# InputOutput.net
KiCad netlist of a schematic drawn in Altium Designer
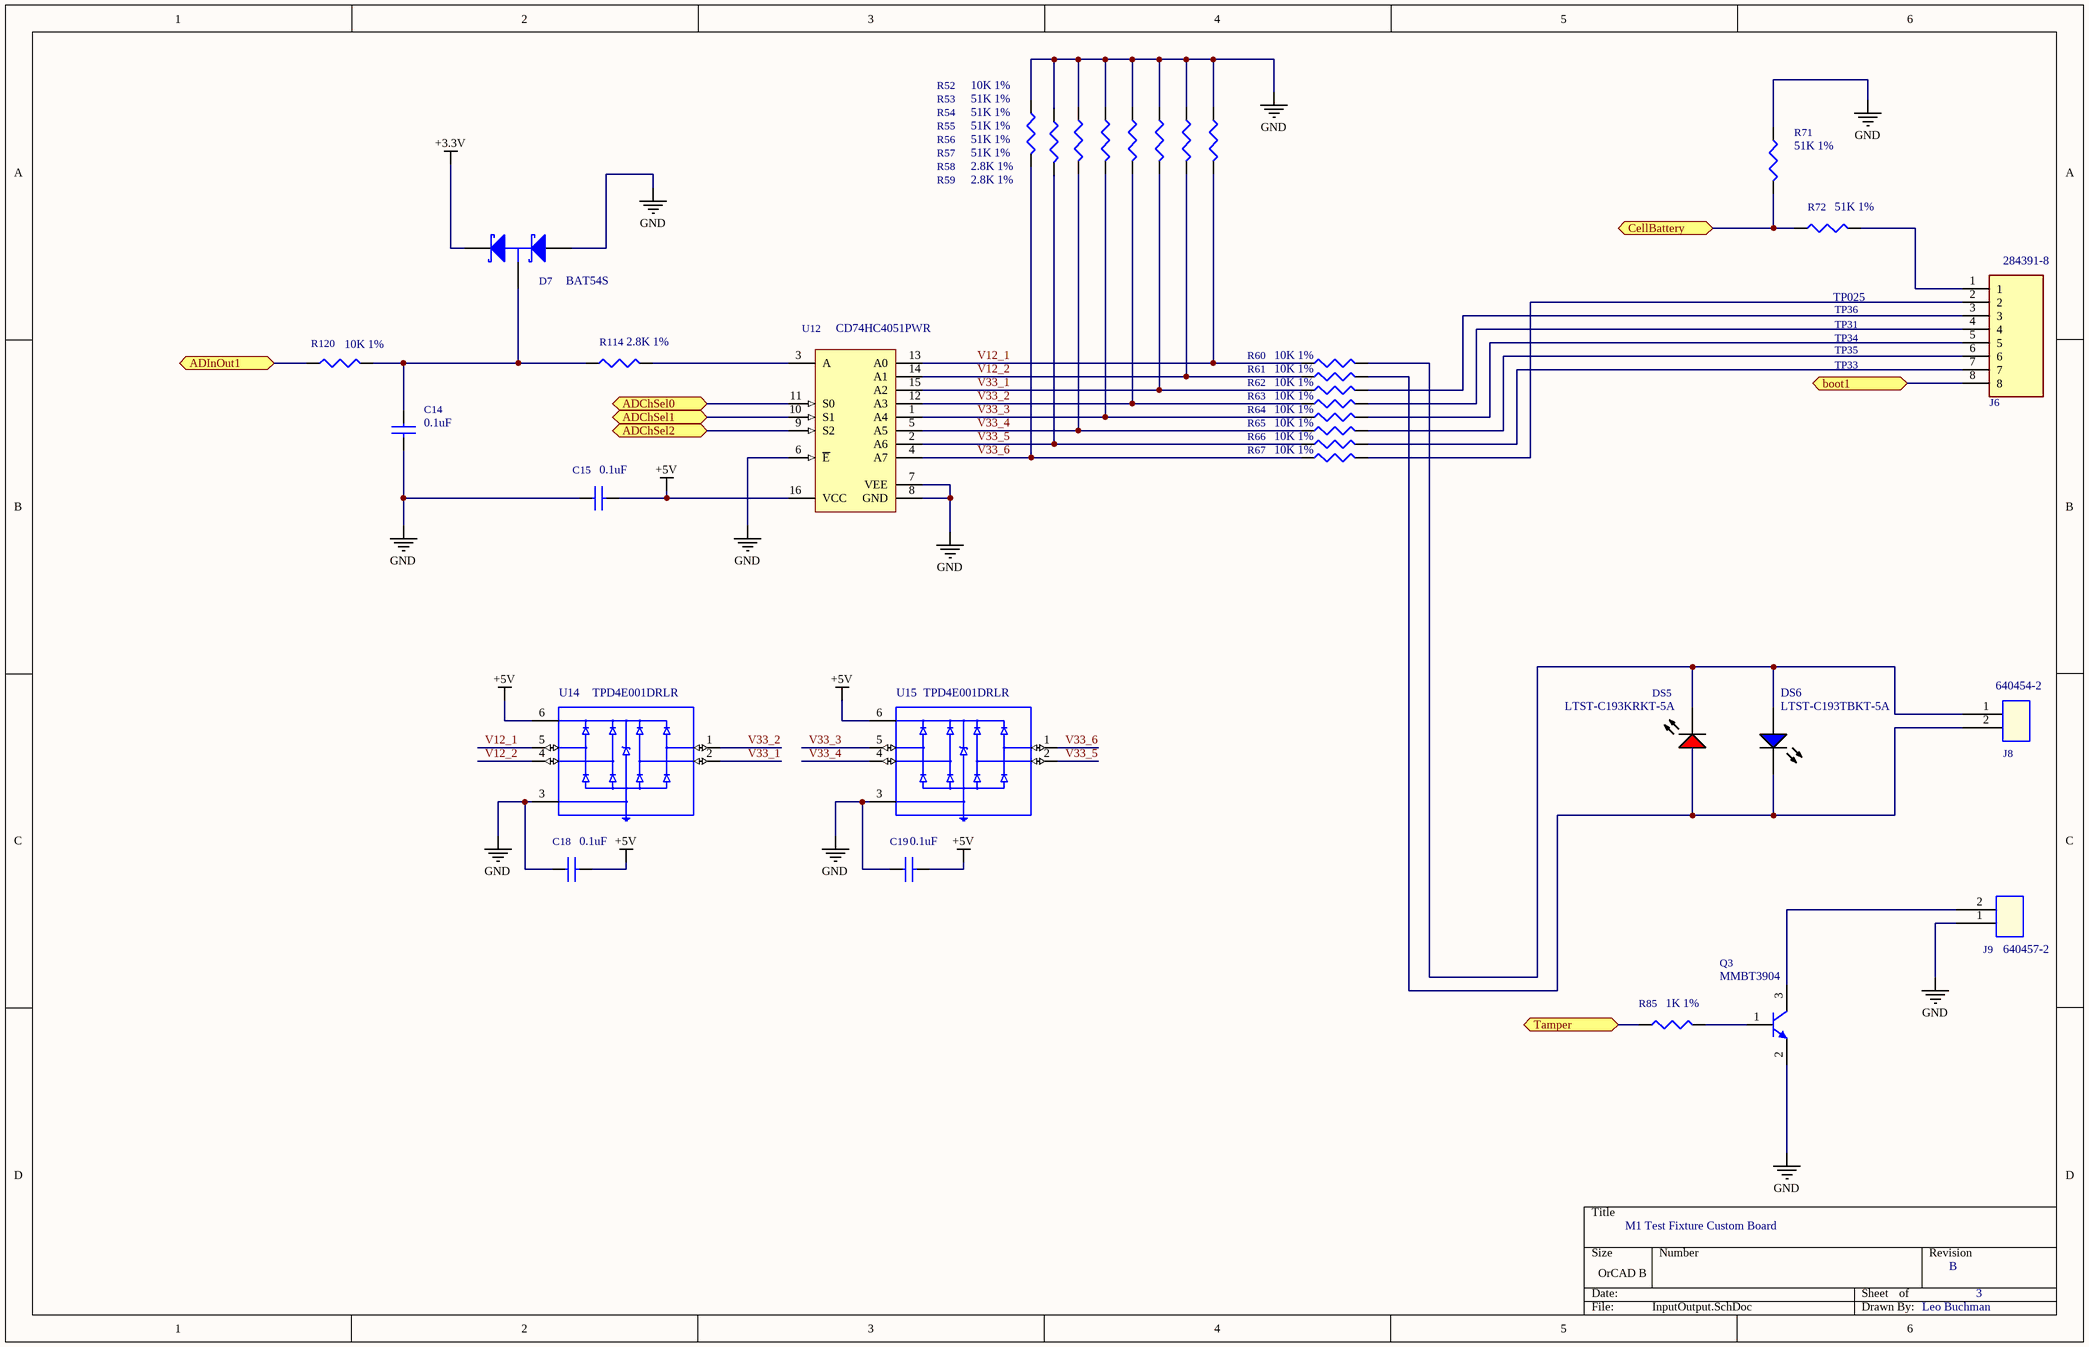
[diagram p0: InputOutput.SchDoc]

(export (version "E")
  (design (tool "Eeschema 10.0.6"))
  (components
    (comp (ref "C14")
      (value "0.1uF")
      (footprint "C0402")
      (description "Cap Ceramic 0.1uF 50V X7R 10% Pad SMD 0402 125C Automotive T/R")
      (fields
        (field (name "MANUFACTURER") "Murata")
        (field (name "MANUFACTURER PART NUMBER") "GRT155R71H104KE01D")
      )
      (libsource (lib "Leo-Home-SQL-Lib") (part "CAPNP"))
    )
    (comp (ref "C15")
      (value "0.1uF")
      (footprint "C0402")
      (description "Cap Ceramic 0.1uF 50V X7R 10% Pad SMD 0402 125C Automotive T/R")
      (fields
        (field (name "MANUFACTURER") "Murata")
        (field (name "MANUFACTURER PART NUMBER") "GRT155R71H104KE01D")
      )
      (libsource (lib "Leo-Home-SQL-Lib") (part "CAPNP"))
    )
    (comp (ref "C18")
      (value "0.1uF")
      (footprint "C0402")
      (description "Cap Ceramic 0.1uF 50V X7R 10% Pad SMD 0402 125C Automotive T/R")
      (fields
        (field (name "MANUFACTURER") "Murata")
        (field (name "MANUFACTURER PART NUMBER") "GRT155R71H104KE01D")
      )
      (libsource (lib "Leo-Home-SQL-Lib") (part "CAPNP"))
    )
    (comp (ref "C19")
      (value "0.1uF")
      (footprint "C0402")
      (description "Cap Ceramic 0.1uF 50V X7R 10% Pad SMD 0402 125C Automotive T/R")
      (fields
        (field (name "MANUFACTURER") "Murata")
        (field (name "MANUFACTURER PART NUMBER") "GRT155R71H104KE01D")
      )
      (libsource (lib "Leo-Home-SQL-Lib") (part "CAPNP"))
    )
    (comp (ref "D7")
      (value "BAT54S")
      (footprint "sot23-3")
      (description "DIODE SCHOTTKY 30V 150MA SOT23-3")
      (fields
        (field (name "MANUFACTURER") "Sangdest Microelectronics")
        (field (name "MANUFACTURER_1") "ON Semiconductor / Fairchild")
      )
      (libsource (lib "Leo-Home-SQL-Lib") (part "BAT54S-7-F"))
    )
    (comp (ref "DS5")
      (value "LTST-C193KRKT-5A")
      (footprint "LED-RED_0603")
      (description "LED RED CLEAR 0603 SMD")
      (fields (field (name "MANUFACTURER") "Vishay Lite-On") (field (name "MANUFACTURER_1") "Broadcom Avago"))
      (libsource (lib "Leo-Home-SQL-Lib") (part "LED-Red"))
    )
    (comp (ref "DS6")
      (value "LTST-C193TBKT-5A")
      (footprint "LED-BLUE_0603")
      (description "LED Blue CLEAR 0603 SMD")
      (fields (field (name "MANUFACTURER") "Vishay Lite-On") (field (name "MANUFACTURER_1") "Rohm"))
      (libsource (lib "Leo-Home-SQL-Lib") (part "LED-Blue"))
    )
    (comp (ref "J6")
      (value "284391-8")
      (footprint "TE_284391-8")
      (description "Conn Terminal Block F 8 POS 3.5mm Solder ST T")
      (fields (field (name "MF") "TE Connectivity") (field (name "DIGI-KEY_PART_NUMBER") "A98163-ND"))
      (libsource (lib "Leo-Home-SQL-Lib") (part "284391-8"))
    )
    (comp (ref "J8")
      (value "640454-2")
      (footprint "CON$5C$2P$5C$100LM")
      (description "Header, Polarized; MTA-100; 2; 250 VAC; Polye")
      (fields (field (name "MANUFACTURER") "TE Connectivity") (field (name "LCSC PART NUMBER") "C86501"))
      (libsource (lib "") (part "S2-CN-0035_1"))
    )
    (comp (ref "J9")
      (value "640457-2")
      (footprint "TE_640457-2")
      (description "MTA-100 HEADER  Friction Lock R/A 2POS 2.54MM")
      (fields
        (field (name "MANUFACTURER") "AMP - TE CONNECTIVITY")
        (field (name "LCSC PART NUMBER") "C86507")
      )
      (libsource (lib "Leo-Home-SQL-Lib") (part "S2-CN-0035"))
    )
    (comp (ref "Q3")
      (value "MMBT3904")
      (footprint "sot23-3")
      (description "Trans GP BJT NPN 60V 0.2A 350mW Automotive 3-Pin SOT-23 T/R")
      (fields (field (name "MANUFACTURER") "ON Semiconductor / Fairchild") (field (name "POWER") "225mW"))
      (libsource (lib "Leo-Home-SQL-Lib") (part "BJT-NPN"))
    )
    (comp (ref "R52")
      (value "10K 1%")
      (footprint "R0402")
      (description "Thick Film 0402 10K OHM 1% 1/16W 0402")
      (fields
        (field (name "MANUFACTURER") "Yageo")
        (field (name "MANUFACTURER PART NUMBER") "RC0402FR-0710KP")
      )
      (libsource (lib "Leo-Home-SQL-Lib") (part "Resistor"))
    )
    (comp (ref "R53")
      (value "51K 1%")
      (footprint "R0402")
      (description "Res Thick Film 0402 51K Ohm 1% 0.063W(1/16W) ±100ppm/C Pad SMD Automotive T/R")
      (fields
        (field (name "MANUFACTURER") "Stackpole Electronics")
        (field (name "MANUFACTURER PART NUMBER") "RMCF0402FT51K0")
      )
      (libsource (lib "Leo-Home-SQL-Lib") (part "Resistor"))
    )
    (comp (ref "R54")
      (value "51K 1%")
      (footprint "R0402")
      (description "Res Thick Film 0402 51K Ohm 1% 0.063W(1/16W) ±100ppm/C Pad SMD Automotive T/R")
      (fields
        (field (name "MANUFACTURER") "Stackpole Electronics")
        (field (name "MANUFACTURER PART NUMBER") "RMCF0402FT51K0")
      )
      (libsource (lib "Leo-Home-SQL-Lib") (part "Resistor"))
    )
    (comp (ref "R55")
      (value "51K 1%")
      (footprint "R0402")
      (description "Res Thick Film 0402 51K Ohm 1% 0.063W(1/16W) ±100ppm/C Pad SMD Automotive T/R")
      (fields
        (field (name "MANUFACTURER") "Stackpole Electronics")
        (field (name "MANUFACTURER PART NUMBER") "RMCF0402FT51K0")
      )
      (libsource (lib "Leo-Home-SQL-Lib") (part "Resistor"))
    )
    (comp (ref "R56")
      (value "51K 1%")
      (footprint "R0402")
      (description "Res Thick Film 0402 51K Ohm 1% 0.063W(1/16W) ±100ppm/C Pad SMD Automotive T/R")
      (fields
        (field (name "MANUFACTURER") "Stackpole Electronics")
        (field (name "MANUFACTURER PART NUMBER") "RMCF0402FT51K0")
      )
      (libsource (lib "Leo-Home-SQL-Lib") (part "Resistor"))
    )
    (comp (ref "R57")
      (value "51K 1%")
      (footprint "R0402")
      (description "Res Thick Film 0402 51K Ohm 1% 0.063W(1/16W) ±100ppm/C Pad SMD Automotive T/R")
      (fields
        (field (name "MANUFACTURER") "Stackpole Electronics")
        (field (name "MANUFACTURER PART NUMBER") "RMCF0402FT51K0")
      )
      (libsource (lib "Leo-Home-SQL-Lib") (part "Resistor"))
    )
    (comp (ref "R58")
      (value "2.8K 1%")
      (footprint "R0402")
      (description "Thick Film 0402 2.8K Ohm 1% 0.063W ±100ppm/°C Molded SMD Paper T/R")
      (fields
        (field (name "MANUFACTURER") "Stackpole Electronics")
        (field (name "MANUFACTURER PART NUMBER") "RMCF0402FT2K80")
      )
      (libsource (lib "Leo-Home-SQL-Lib") (part "Resistor"))
    )
    (comp (ref "R59")
      (value "2.8K 1%")
      (footprint "R0402")
      (description "Thick Film 0402 2.8K Ohm 1% 0.063W ±100ppm/°C Molded SMD Paper T/R")
      (fields
        (field (name "MANUFACTURER") "Stackpole Electronics")
        (field (name "MANUFACTURER PART NUMBER") "RMCF0402FT2K80")
      )
      (libsource (lib "Leo-Home-SQL-Lib") (part "Resistor"))
    )
    (comp (ref "R60")
      (value "10K 1%")
      (footprint "R0402")
      (description "Thick Film 0402 10K OHM 1% 1/16W 0402")
      (fields
        (field (name "MANUFACTURER") "Yageo")
        (field (name "MANUFACTURER PART NUMBER") "RC0402FR-0710KP")
      )
      (libsource (lib "Leo-Home-SQL-Lib") (part "Resistor"))
    )
    (comp (ref "R61")
      (value "10K 1%")
      (footprint "R0402")
      (description "Thick Film 0402 10K OHM 1% 1/16W 0402")
      (fields
        (field (name "MANUFACTURER") "Yageo")
        (field (name "MANUFACTURER PART NUMBER") "RC0402FR-0710KP")
      )
      (libsource (lib "Leo-Home-SQL-Lib") (part "Resistor"))
    )
    (comp (ref "R62")
      (value "10K 1%")
      (footprint "R0402")
      (description "Thick Film 0402 10K OHM 1% 1/16W 0402")
      (fields
        (field (name "MANUFACTURER") "Yageo")
        (field (name "MANUFACTURER PART NUMBER") "RC0402FR-0710KP")
      )
      (libsource (lib "Leo-Home-SQL-Lib") (part "Resistor"))
    )
    (comp (ref "R63")
      (value "10K 1%")
      (footprint "R0402")
      (description "Thick Film 0402 10K OHM 1% 1/16W 0402")
      (fields
        (field (name "MANUFACTURER") "Yageo")
        (field (name "MANUFACTURER PART NUMBER") "RC0402FR-0710KP")
      )
      (libsource (lib "Leo-Home-SQL-Lib") (part "Resistor"))
    )
    (comp (ref "R64")
      (value "10K 1%")
      (footprint "R0402")
      (description "Thick Film 0402 10K OHM 1% 1/16W 0402")
      (fields
        (field (name "MANUFACTURER") "Yageo")
        (field (name "MANUFACTURER PART NUMBER") "RC0402FR-0710KP")
      )
      (libsource (lib "Leo-Home-SQL-Lib") (part "Resistor"))
    )
    (comp (ref "R65")
      (value "10K 1%")
      (footprint "R0402")
      (description "Thick Film 0402 10K OHM 1% 1/16W 0402")
      (fields
        (field (name "MANUFACTURER") "Yageo")
        (field (name "MANUFACTURER PART NUMBER") "RC0402FR-0710KP")
      )
      (libsource (lib "Leo-Home-SQL-Lib") (part "Resistor"))
    )
    (comp (ref "R66")
      (value "10K 1%")
      (footprint "R0402")
      (description "Thick Film 0402 10K OHM 1% 1/16W 0402")
      (fields
        (field (name "MANUFACTURER") "Yageo")
        (field (name "MANUFACTURER PART NUMBER") "RC0402FR-0710KP")
      )
      (libsource (lib "Leo-Home-SQL-Lib") (part "Resistor"))
    )
    (comp (ref "R67")
      (value "10K 1%")
      (footprint "R0402")
      (description "Thick Film 0402 10K OHM 1% 1/16W 0402")
      (fields
        (field (name "MANUFACTURER") "Yageo")
        (field (name "MANUFACTURER PART NUMBER") "RC0402FR-0710KP")
      )
      (libsource (lib "Leo-Home-SQL-Lib") (part "Resistor"))
    )
    (comp (ref "R71")
      (value "51K 1%")
      (footprint "R0402")
      (description "Res Thick Film 0402 51K Ohm 1% 0.063W(1/16W) ±100ppm/C Pad SMD Automotive T/R")
      (fields
        (field (name "MANUFACTURER") "Stackpole Electronics")
        (field (name "MANUFACTURER PART NUMBER") "RMCF0402FT51K0")
      )
      (libsource (lib "Leo-Home-SQL-Lib") (part "Resistor"))
    )
    (comp (ref "R72")
      (value "51K 1%")
      (footprint "R0402")
      (description "Res Thick Film 0402 51K Ohm 1% 0.063W(1/16W) ±100ppm/C Pad SMD Automotive T/R")
      (fields
        (field (name "MANUFACTURER") "Stackpole Electronics")
        (field (name "MANUFACTURER PART NUMBER") "RMCF0402FT51K0")
      )
      (libsource (lib "Leo-Home-SQL-Lib") (part "Resistor"))
    )
    (comp (ref "R85")
      (value "1K 1%")
      (footprint "R0402")
      (description "Thick Film 0402 1K Ohm 1% 1/8W 0402")
      (fields
        (field (name "MANUFACTURER") "TE Connectivity")
        (field (name "MANUFACTURER PART NUMBER") "CRGP0402F1K0")
      )
      (libsource (lib "Leo-Home-SQL-Lib") (part "Resistor"))
    )
    (comp (ref "R114")
      (value "2.8K 1%")
      (footprint "R0402")
      (description "Thick Film 0402 2.8K Ohm 1% 0.063W ±100ppm/°C Molded SMD Paper T/R")
      (fields
        (field (name "MANUFACTURER") "Stackpole Electronics")
        (field (name "MANUFACTURER PART NUMBER") "RMCF0402FT2K80")
      )
      (libsource (lib "Leo-Home-SQL-Lib") (part "Resistor"))
    )
    (comp (ref "R120")
      (value "10K 1%")
      (footprint "R0402")
      (description "Thick Film 0402 10K OHM 1% 1/16W 0402")
      (fields
        (field (name "MANUFACTURER") "Yageo")
        (field (name "MANUFACTURER PART NUMBER") "RC0402FR-0710KP")
      )
      (libsource (lib "Leo-Home-SQL-Lib") (part "Resistor"))
    )
    (comp (ref "U12")
      (value "CD74HC4051PWR")
      (footprint "16-TSSOP-4.4mm")
      (description "5-V, 8: 1, 1-channel analog mutliplexer 16-TS")
      (fields
        (field (name "GENERIC PART NUMBER") "CD74HC4051")
        (field (name "MANUFACTURER") "Texas Instruments")
      )
      (libsource (lib "Leo-Home-SQL-Lib") (part "CMP-1575-00038-4_1"))
    )
    (comp (ref "U14")
      (value "TPD4E001DRLR")
      (footprint "SOTFL50P160X60-6N")
      (description "TVS DIODE 5.5VWM SOT6")
      (fields (field (name "MANUFACTURER") "Texas Instruments") (field (name "LCSC PART NUMBER") "C527516"))
      (libsource (lib "Leo-Home-SQL-Lib") (part "TPD4E001DRLR"))
    )
    (comp (ref "U15")
      (value "TPD4E001DRLR")
      (footprint "SOTFL50P160X60-6N")
      (description "TVS DIODE 5.5VWM SOT6")
      (fields (field (name "MANUFACTURER") "Texas Instruments") (field (name "LCSC PART NUMBER") "C527516"))
      (libsource (lib "Leo-Home-SQL-Lib") (part "TPD4E001DRLR"))
    )
  )
  (nets
    (net (code "1") (name "+3.3V") (class "Default")
      (node (ref "D7") (pin "2") (pinfunction "K_2") (pintype "passive"))
    )
    (net (code "2") (name "+5V") (class "Default")
      (node (ref "C15") (pin "2") (pinfunction "2_2") (pintype "passive"))
      (node (ref "C18") (pin "2") (pinfunction "2_2") (pintype "passive"))
      (node (ref "C19") (pin "2") (pinfunction "2_2") (pintype "passive"))
      (node (ref "U12") (pin "16") (pinfunction "VCC_16") (pintype "power_in"))
      (node (ref "U14") (pin "6") (pinfunction "VCC_6") (pintype "power_in"))
      (node (ref "U15") (pin "6") (pinfunction "VCC_6") (pintype "power_in"))
    )
    (net (code "3") (name "/ADChSel0") (class "Default")
      (node (ref "U12") (pin "11") (pinfunction "S0_11") (pintype "input"))
    )
    (net (code "4") (name "/ADChSel1") (class "Default")
      (node (ref "U12") (pin "10") (pinfunction "S1_10") (pintype "input"))
    )
    (net (code "5") (name "/ADChSel2") (class "Default")
      (node (ref "U12") (pin "9") (pinfunction "S2_9") (pintype "input"))
    )
    (net (code "6") (name "/ADInOut1") (class "Default")
      (node (ref "R120") (pin "1") (pinfunction "1_1") (pintype "passive"))
    )
    (net (code "7") (name "/CellBattery") (class "Default")
      (node (ref "R71") (pin "2") (pinfunction "2_2") (pintype "passive"))
      (node (ref "R72") (pin "1") (pinfunction "1_1") (pintype "passive"))
    )
    (net (code "8") (name "/Tamper") (class "Default")
      (node (ref "R85") (pin "1") (pinfunction "1_1") (pintype "passive"))
    )
    (net (code "9") (name "/V12_1") (class "Default")
      (node (ref "R59") (pin "2") (pinfunction "2_2") (pintype "passive"))
      (node (ref "R60") (pin "1") (pinfunction "1_1") (pintype "passive"))
      (node (ref "U12") (pin "13") (pinfunction "A0_13") (pintype "passive"))
      (node (ref "U14") (pin "5") (pinfunction "IO4_5") (pintype "bidirectional"))
    )
    (net (code "10") (name "/V12_2") (class "Default")
      (node (ref "R58") (pin "2") (pinfunction "2_2") (pintype "passive"))
      (node (ref "R61") (pin "1") (pinfunction "1_1") (pintype "passive"))
      (node (ref "U12") (pin "14") (pinfunction "A1_14") (pintype "passive"))
      (node (ref "U14") (pin "4") (pinfunction "IO3_4") (pintype "bidirectional"))
    )
    (net (code "11") (name "/V33_1") (class "Default")
      (node (ref "R57") (pin "2") (pinfunction "2_2") (pintype "passive"))
      (node (ref "R62") (pin "1") (pinfunction "1_1") (pintype "passive"))
      (node (ref "U12") (pin "15") (pinfunction "A2_15") (pintype "passive"))
      (node (ref "U14") (pin "2") (pinfunction "IO2_2") (pintype "bidirectional"))
    )
    (net (code "12") (name "/V33_2") (class "Default")
      (node (ref "R56") (pin "2") (pinfunction "2_2") (pintype "passive"))
      (node (ref "R63") (pin "1") (pinfunction "1_1") (pintype "passive"))
      (node (ref "U12") (pin "12") (pinfunction "A3_12") (pintype "passive"))
      (node (ref "U14") (pin "1") (pinfunction "IO1_1") (pintype "bidirectional"))
    )
    (net (code "13") (name "/V33_3") (class "Default")
      (node (ref "R55") (pin "2") (pinfunction "2_2") (pintype "passive"))
      (node (ref "R64") (pin "1") (pinfunction "1_1") (pintype "passive"))
      (node (ref "U12") (pin "1") (pinfunction "A4_1") (pintype "passive"))
      (node (ref "U15") (pin "5") (pinfunction "IO4_5") (pintype "bidirectional"))
    )
    (net (code "14") (name "/V33_4") (class "Default")
      (node (ref "R54") (pin "2") (pinfunction "2_2") (pintype "passive"))
      (node (ref "R65") (pin "1") (pinfunction "1_1") (pintype "passive"))
      (node (ref "U12") (pin "5") (pinfunction "A5_5") (pintype "passive"))
      (node (ref "U15") (pin "4") (pinfunction "IO3_4") (pintype "bidirectional"))
    )
    (net (code "15") (name "/V33_5") (class "Default")
      (node (ref "R53") (pin "2") (pinfunction "2_2") (pintype "passive"))
      (node (ref "R66") (pin "1") (pinfunction "1_1") (pintype "passive"))
      (node (ref "U12") (pin "2") (pinfunction "A6_2") (pintype "passive"))
      (node (ref "U15") (pin "2") (pinfunction "IO2_2") (pintype "bidirectional"))
    )
    (net (code "16") (name "/V33_6") (class "Default")
      (node (ref "R52") (pin "2") (pinfunction "2_2") (pintype "passive"))
      (node (ref "R67") (pin "1") (pinfunction "1_1") (pintype "passive"))
      (node (ref "U12") (pin "4") (pinfunction "A7_4") (pintype "passive"))
      (node (ref "U15") (pin "1") (pinfunction "IO1_1") (pintype "bidirectional"))
    )
    (net (code "17") (name "/boot1") (class "Default")
      (node (ref "J6") (pin "8") (pinfunction "8_8") (pintype "passive"))
    )
    (net (code "18") (name "GND") (class "Default")
      (node (ref "C14") (pin "2") (pinfunction "2_2") (pintype "passive"))
      (node (ref "C15") (pin "1") (pinfunction "1_1") (pintype "passive"))
      (node (ref "C18") (pin "1") (pinfunction "1_1") (pintype "passive"))
      (node (ref "C19") (pin "1") (pinfunction "1_1") (pintype "passive"))
      (node (ref "D7") (pin "1") (pinfunction "A_1") (pintype "passive"))
      (node (ref "J9") (pin "1") (pinfunction "1_1") (pintype "passive"))
      (node (ref "Q3") (pin "2") (pinfunction "E_2") (pintype "passive"))
      (node (ref "R52") (pin "1") (pinfunction "1_1") (pintype "passive"))
      (node (ref "R53") (pin "1") (pinfunction "1_1") (pintype "passive"))
      (node (ref "R54") (pin "1") (pinfunction "1_1") (pintype "passive"))
      (node (ref "R55") (pin "1") (pinfunction "1_1") (pintype "passive"))
      (node (ref "R56") (pin "1") (pinfunction "1_1") (pintype "passive"))
      (node (ref "R57") (pin "1") (pinfunction "1_1") (pintype "passive"))
      (node (ref "R58") (pin "1") (pinfunction "1_1") (pintype "passive"))
      (node (ref "R59") (pin "1") (pinfunction "1_1") (pintype "passive"))
      (node (ref "R71") (pin "1") (pinfunction "1_1") (pintype "passive"))
      (node (ref "U12") (pin "6") (pinfunction "~{E}_6") (pintype "input"))
      (node (ref "U12") (pin "7") (pinfunction "VEE_7") (pintype "power_in"))
      (node (ref "U12") (pin "8") (pinfunction "GND_8") (pintype "power_in"))
      (node (ref "U14") (pin "3") (pinfunction "GND_3") (pintype "power_in"))
      (node (ref "U15") (pin "3") (pinfunction "GND_3") (pintype "power_in"))
    )
    (net (code "19") (name "Net-(D7-C)") (class "Default")
      (node (ref "C14") (pin "1") (pinfunction "1_1") (pintype "passive"))
      (node (ref "D7") (pin "3") (pinfunction "C_3") (pintype "passive"))
      (node (ref "R114") (pin "1") (pinfunction "1_1") (pintype "passive"))
      (node (ref "R120") (pin "2") (pinfunction "2_2") (pintype "passive"))
    )
    (net (code "20") (name "Net-(DS5-A)") (class "Default")
      (node (ref "DS5") (pin "1") (pinfunction "A_1") (pintype "passive"))
      (node (ref "DS6") (pin "2") (pinfunction "K_2") (pintype "passive"))
      (node (ref "J8") (pin "2") (pinfunction "2_2") (pintype "passive"))
      (node (ref "R61") (pin "2") (pinfunction "2_2") (pintype "passive"))
    )
    (net (code "21") (name "Net-(DS5-K)") (class "Default")
      (node (ref "DS5") (pin "2") (pinfunction "K_2") (pintype "passive"))
      (node (ref "DS6") (pin "1") (pinfunction "A_1") (pintype "passive"))
      (node (ref "J8") (pin "1") (pinfunction "1_1") (pintype "passive"))
      (node (ref "R60") (pin "2") (pinfunction "2_2") (pintype "passive"))
    )
    (net (code "22") (name "Net-(J6-Pad1)") (class "Default")
      (node (ref "J6") (pin "1") (pinfunction "1_1") (pintype "passive"))
      (node (ref "R72") (pin "2") (pinfunction "2_2") (pintype "passive"))
    )
    (net (code "23") (name "Net-(J6-Pad2)") (class "Default")
      (node (ref "J6") (pin "2") (pinfunction "2_2") (pintype "passive"))
      (node (ref "R67") (pin "2") (pinfunction "2_2") (pintype "passive"))
    )
    (net (code "24") (name "Net-(J6-Pad3)") (class "Default")
      (node (ref "J6") (pin "3") (pinfunction "3_3") (pintype "passive"))
      (node (ref "R62") (pin "2") (pinfunction "2_2") (pintype "passive"))
    )
    (net (code "25") (name "Net-(J6-Pad4)") (class "Default")
      (node (ref "J6") (pin "4") (pinfunction "4_4") (pintype "passive"))
      (node (ref "R63") (pin "2") (pinfunction "2_2") (pintype "passive"))
    )
    (net (code "26") (name "Net-(J6-Pad5)") (class "Default")
      (node (ref "J6") (pin "5") (pinfunction "5_5") (pintype "passive"))
      (node (ref "R64") (pin "2") (pinfunction "2_2") (pintype "passive"))
    )
    (net (code "27") (name "Net-(J6-Pad6)") (class "Default")
      (node (ref "J6") (pin "6") (pinfunction "6_6") (pintype "passive"))
      (node (ref "R65") (pin "2") (pinfunction "2_2") (pintype "passive"))
    )
    (net (code "28") (name "Net-(J6-Pad7)") (class "Default")
      (node (ref "J6") (pin "7") (pinfunction "7_7") (pintype "passive"))
      (node (ref "R66") (pin "2") (pinfunction "2_2") (pintype "passive"))
    )
    (net (code "29") (name "Net-(Q3-B)") (class "Default")
      (node (ref "Q3") (pin "1") (pinfunction "B_1") (pintype "passive"))
      (node (ref "R85") (pin "2") (pinfunction "2_2") (pintype "passive"))
    )
    (net (code "30") (name "Net-(Q3-C)") (class "Default")
      (node (ref "J9") (pin "2") (pinfunction "2_2") (pintype "passive"))
      (node (ref "Q3") (pin "3") (pinfunction "C_3") (pintype "passive"))
    )
    (net (code "31") (name "Net-(U12-A)") (class "Default")
      (node (ref "R114") (pin "2") (pinfunction "2_2") (pintype "passive"))
      (node (ref "U12") (pin "3") (pinfunction "A_3") (pintype "passive"))
    )
  )
)
